# LED.net
KiCad netlist of a schematic drawn in Altium Designer
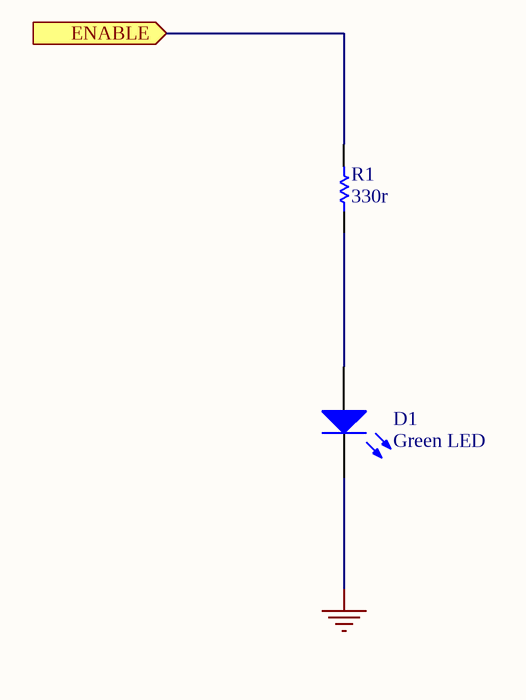
[diagram p0: LED.SchDoc]

(export (version "E")
  (design (tool "Eeschema 10.0.6"))
  (components
    (comp (ref "D1")
      (value "Green LED")
      (footprint "LED 0805")
      (description "Typical INFRARED GaAs LED")
      (fields (field (name "PUBLISHER") "Altium Limited"))
      (libsource (lib "Miscellaneous Devices") (part "LED0"))
    )
    (comp (ref "R1")
      (value "330r")
      (footprint "RESC1608N")
      (description "Resistor")
      (fields (field (name "PUBLISHER") "Altium Limited"))
      (libsource (lib "Miscellaneous Devices") (part "Res1"))
    )
  )
  (nets
    (net (code "1") (name "/ENABLE") (class "Default")
      (node (ref "R1") (pin "2") (pinfunction "2_2") (pintype "passive"))
    )
    (net (code "2") (name "GND") (class "Default")
      (node (ref "D1") (pin "2") (pinfunction "K_2") (pintype "passive"))
    )
    (net (code "3") (name "Net-(D1-A)") (class "Default")
      (node (ref "D1") (pin "1") (pinfunction "A_1") (pintype "passive"))
      (node (ref "R1") (pin "1") (pinfunction "1_1") (pintype "passive"))
    )
  )
)
